# M710X.net
KiCad netlist of a schematic drawn in EAGLE
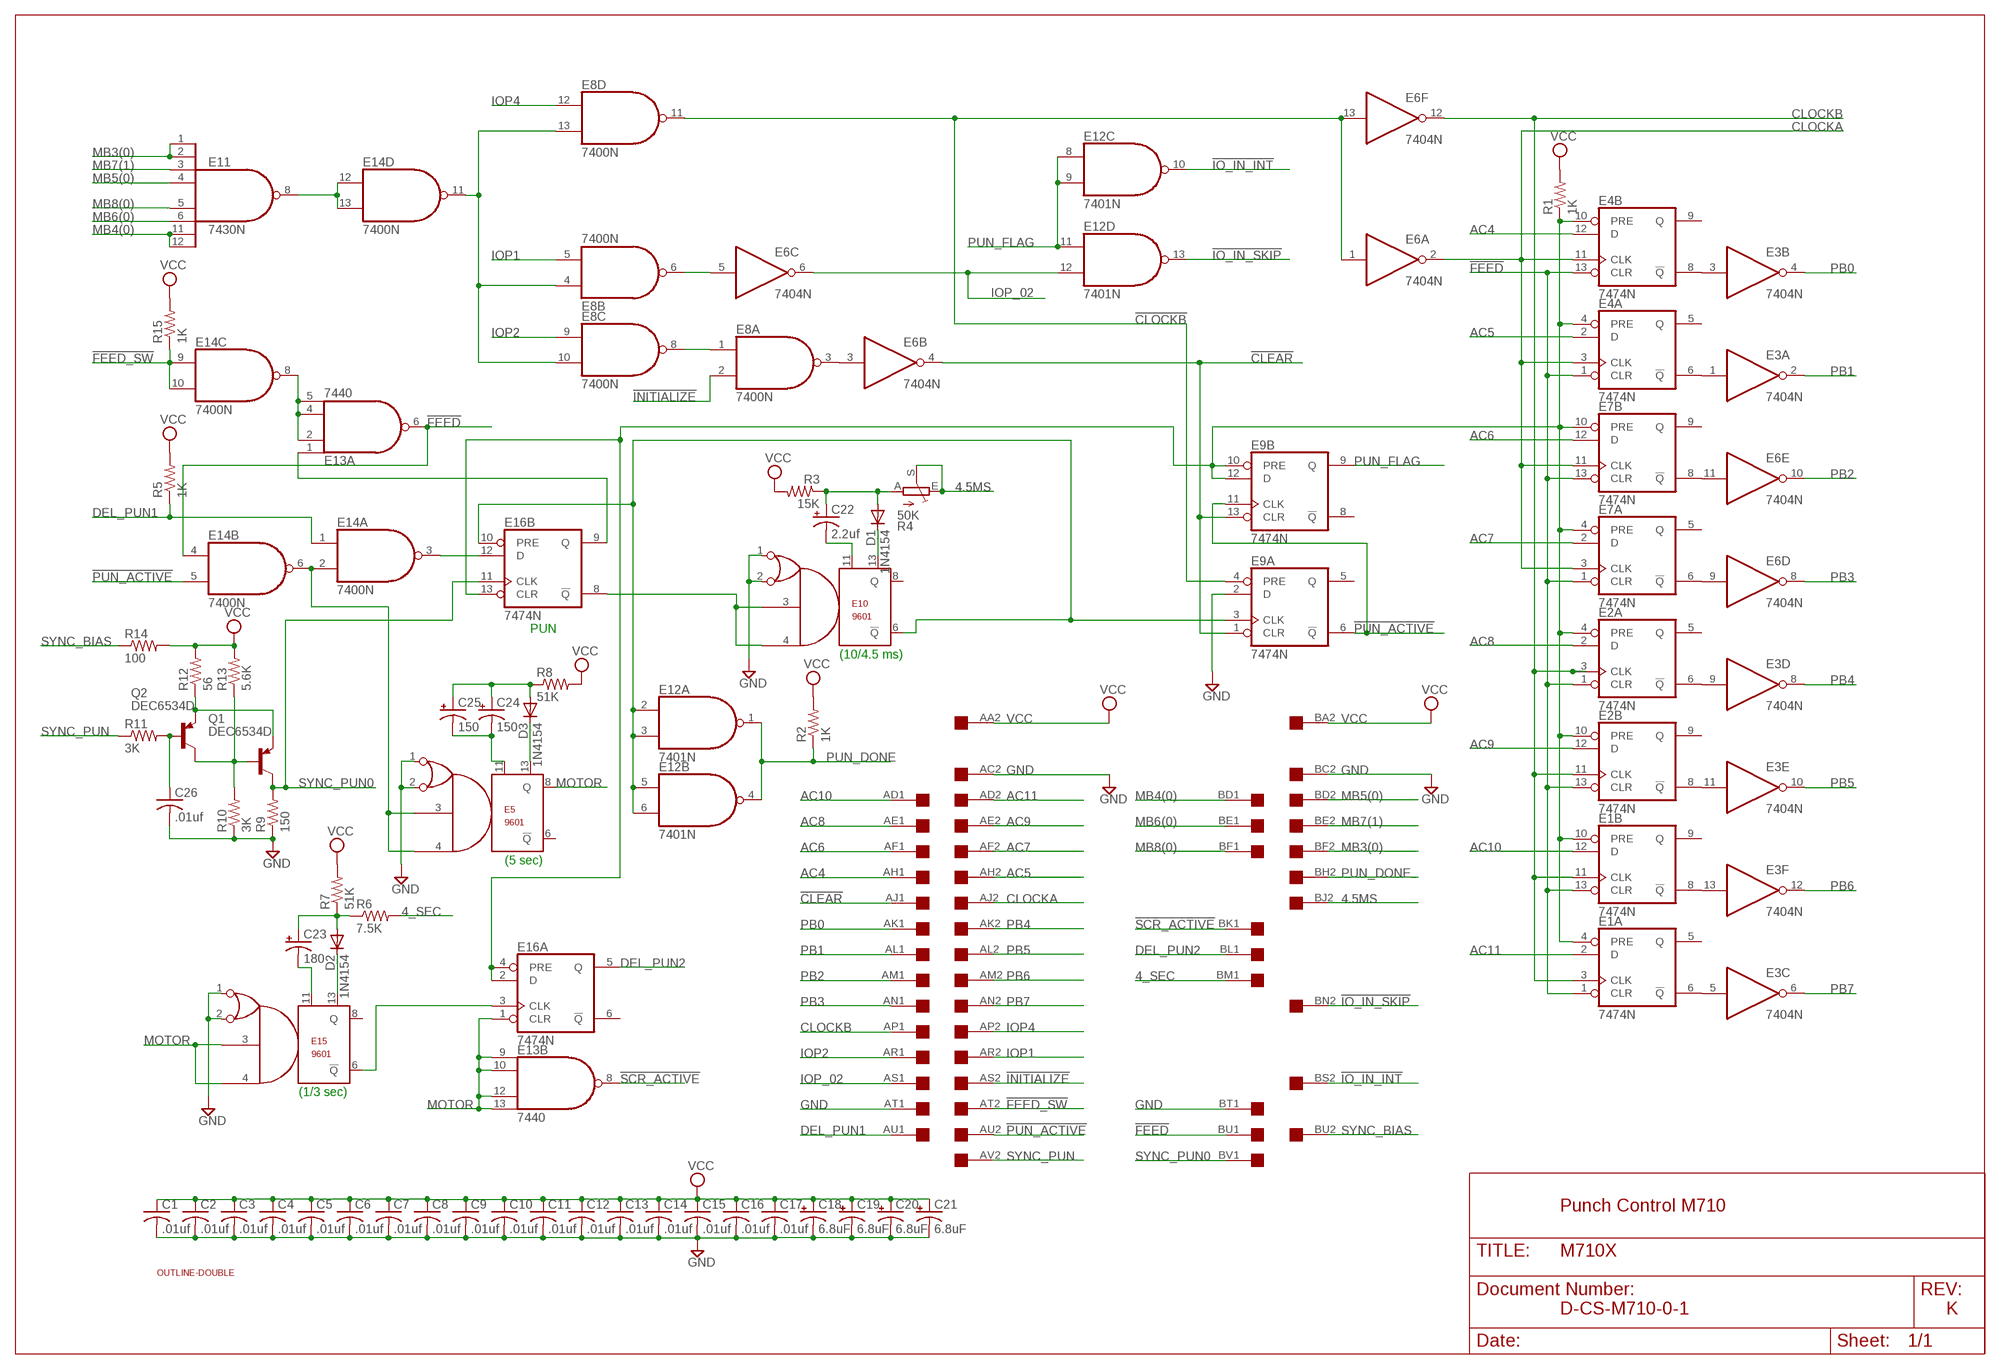
[diagram p0: schematic, sheet 1]

(export (version "E")
  (design (tool "Eeschema 10.0.6"))
  (components
    (comp (ref "C1")
      (value ".01uf")
      (footprint "eagle-import:C050-025X075")
      (libsource (lib "eagle-import") (part "C-US050-025X075"))
    )
    (comp (ref "C2")
      (value ".01uf")
      (footprint "eagle-import:C050-025X075")
      (libsource (lib "eagle-import") (part "C-US050-025X075"))
    )
    (comp (ref "C3")
      (value ".01uf")
      (footprint "eagle-import:C050-025X075")
      (libsource (lib "eagle-import") (part "C-US050-025X075"))
    )
    (comp (ref "C4")
      (value ".01uf")
      (footprint "eagle-import:C050-025X075")
      (libsource (lib "eagle-import") (part "C-US050-025X075"))
    )
    (comp (ref "C5")
      (value ".01uf")
      (footprint "eagle-import:C050-025X075")
      (libsource (lib "eagle-import") (part "C-US050-025X075"))
    )
    (comp (ref "C6")
      (value ".01uf")
      (footprint "eagle-import:C050-025X075")
      (libsource (lib "eagle-import") (part "C-US050-025X075"))
    )
    (comp (ref "C7")
      (value ".01uf")
      (footprint "eagle-import:C050-025X075")
      (libsource (lib "eagle-import") (part "C-US050-025X075"))
    )
    (comp (ref "C8")
      (value ".01uf")
      (footprint "eagle-import:C050-025X075")
      (libsource (lib "eagle-import") (part "C-US050-025X075"))
    )
    (comp (ref "C9")
      (value ".01uf")
      (footprint "eagle-import:C050-025X075")
      (libsource (lib "eagle-import") (part "C-US050-025X075"))
    )
    (comp (ref "C10")
      (value ".01uf")
      (footprint "eagle-import:C050-025X075")
      (libsource (lib "eagle-import") (part "C-US050-025X075"))
    )
    (comp (ref "C11")
      (value ".01uf")
      (footprint "eagle-import:C050-025X075")
      (libsource (lib "eagle-import") (part "C-US050-025X075"))
    )
    (comp (ref "C12")
      (value ".01uf")
      (footprint "eagle-import:C050-025X075")
      (libsource (lib "eagle-import") (part "C-US050-025X075"))
    )
    (comp (ref "C13")
      (value ".01uf")
      (footprint "eagle-import:C050-025X075")
      (libsource (lib "eagle-import") (part "C-US050-025X075"))
    )
    (comp (ref "C14")
      (value ".01uf")
      (footprint "eagle-import:C050-025X075")
      (libsource (lib "eagle-import") (part "C-US050-025X075"))
    )
    (comp (ref "C15")
      (value ".01uf")
      (footprint "eagle-import:C050-025X075")
      (libsource (lib "eagle-import") (part "C-US050-025X075"))
    )
    (comp (ref "C16")
      (value ".01uf")
      (footprint "eagle-import:C050-025X075")
      (libsource (lib "eagle-import") (part "C-US050-025X075"))
    )
    (comp (ref "C17")
      (value ".01uf")
      (footprint "eagle-import:C050-025X075")
      (libsource (lib "eagle-import") (part "C-US050-025X075"))
    )
    (comp (ref "C18")
      (value "6.8uF")
      (footprint "eagle-import:E12-8")
      (libsource (lib "eagle-import") (part "CPOL-USE20-8AXIAL"))
    )
    (comp (ref "C19")
      (value "6.8uF")
      (footprint "eagle-import:E12-8")
      (libsource (lib "eagle-import") (part "CPOL-USE20-8AXIAL"))
    )
    (comp (ref "C20")
      (value "6.8uF")
      (footprint "eagle-import:E12-8")
      (libsource (lib "eagle-import") (part "CPOL-USE20-8AXIAL"))
    )
    (comp (ref "C21")
      (value "6.8uF")
      (footprint "eagle-import:E12-8")
      (libsource (lib "eagle-import") (part "CPOL-USE20-8AXIAL"))
    )
    (comp (ref "C22")
      (value "2.2uf")
      (footprint "eagle-import:E15-5")
      (libsource (lib "eagle-import") (part "CPOL-USE15-5AXIAL"))
    )
    (comp (ref "C23")
      (value "180")
      (footprint "eagle-import:E12-8")
      (libsource (lib "eagle-import") (part "CPOL-USE20-8AXIAL"))
    )
    (comp (ref "C24")
      (value "150")
      (footprint "eagle-import:E22-6")
      (libsource (lib "eagle-import") (part "CPOL-USE22-6AXIAL"))
    )
    (comp (ref "C25")
      (value "150")
      (footprint "eagle-import:E22-6")
      (libsource (lib "eagle-import") (part "CPOL-USE22-6AXIAL"))
    )
    (comp (ref "C26")
      (value ".01uf")
      (footprint "eagle-import:C050-025X075")
      (libsource (lib "eagle-import") (part "C-US050-025X075"))
    )
    (comp (ref "D1")
      (value "1N4154")
      (footprint "eagle-import:DO41-10")
      (libsource (lib "eagle-import") (part "1N4004"))
    )
    (comp (ref "D2")
      (value "1N4154")
      (footprint "eagle-import:DO41-10")
      (libsource (lib "eagle-import") (part "1N4004"))
    )
    (comp (ref "D3")
      (value "1N4154")
      (footprint "eagle-import:DO41-10")
      (libsource (lib "eagle-import") (part "1N4004"))
    )
    (comp (ref "E1")
      (value "7474N")
      (footprint "eagle-import:DIL14")
      (libsource (lib "eagle-import") (part "7474NS"))
    )
    (comp (ref "E2")
      (value "7474N")
      (footprint "eagle-import:DIL14")
      (libsource (lib "eagle-import") (part "7474NS"))
    )
    (comp (ref "E3")
      (value "7404N")
      (footprint "eagle-import:DIL14")
      (libsource (lib "eagle-import") (part "7404N"))
    )
    (comp (ref "E4")
      (value "7474N")
      (footprint "eagle-import:DIL14")
      (libsource (lib "eagle-import") (part "7474NS"))
    )
    (comp (ref "E5")
      (value "9601")
      (footprint "eagle-import:DIL14")
      (libsource (lib "eagle-import") (part "9601"))
    )
    (comp (ref "E6")
      (value "7404N")
      (footprint "eagle-import:DIL14")
      (libsource (lib "eagle-import") (part "7404N"))
    )
    (comp (ref "E7")
      (value "7474N")
      (footprint "eagle-import:DIL14")
      (libsource (lib "eagle-import") (part "7474NS"))
    )
    (comp (ref "E8")
      (value "7400N")
      (footprint "eagle-import:DIL14")
      (libsource (lib "eagle-import") (part "7400N"))
    )
    (comp (ref "E9")
      (value "7474N")
      (footprint "eagle-import:DIL14")
      (libsource (lib "eagle-import") (part "7474NS"))
    )
    (comp (ref "E10")
      (value "9601")
      (footprint "eagle-import:DIL14")
      (libsource (lib "eagle-import") (part "9601"))
    )
    (comp (ref "E11")
      (value "7430N")
      (footprint "eagle-import:DIL14")
      (libsource (lib "eagle-import") (part "7430N"))
    )
    (comp (ref "E12")
      (value "7401N")
      (footprint "eagle-import:DIL14")
      (libsource (lib "eagle-import") (part "7401NLS"))
    )
    (comp (ref "E13")
      (value "7440")
      (footprint "eagle-import:DIL14")
      (libsource (lib "eagle-import") (part "7420NS"))
    )
    (comp (ref "E14")
      (value "7400N")
      (footprint "eagle-import:DIL14")
      (libsource (lib "eagle-import") (part "7400N"))
    )
    (comp (ref "E15")
      (value "9601")
      (footprint "eagle-import:DIL14")
      (libsource (lib "eagle-import") (part "9601"))
    )
    (comp (ref "E16")
      (value "7474N")
      (footprint "eagle-import:DIL14")
      (libsource (lib "eagle-import") (part "7474NS"))
    )
    (comp (ref "Q1")
      (value "DEC6534D")
      (footprint "eagle-import:TO5")
      (libsource (lib "eagle-import") (part "2N2905"))
    )
    (comp (ref "Q2")
      (value "DEC6534D")
      (footprint "eagle-import:TO5")
      (libsource (lib "eagle-import") (part "2N2905"))
    )
    (comp (ref "R1")
      (value "1K")
      (footprint "eagle-import:0207_10")
      (libsource (lib "eagle-import") (part "R-US_0207/10"))
    )
    (comp (ref "R2")
      (value "1K")
      (footprint "eagle-import:0207_10")
      (libsource (lib "eagle-import") (part "R-US_0207/10"))
    )
    (comp (ref "R3")
      (value "15K")
      (footprint "eagle-import:0207_10")
      (libsource (lib "eagle-import") (part "R-US_0207/10"))
    )
    (comp (ref "R4")
      (value "50K")
      (footprint "eagle-import:RJ6")
      (libsource (lib "eagle-import") (part "TRIM_EU-RJ6"))
    )
    (comp (ref "R5")
      (value "1K")
      (footprint "eagle-import:0207_10")
      (libsource (lib "eagle-import") (part "R-US_0207/10"))
    )
    (comp (ref "R6")
      (value "7.5K")
      (footprint "eagle-import:0207_10")
      (libsource (lib "eagle-import") (part "R-US_0207/10"))
    )
    (comp (ref "R7")
      (value "51K")
      (footprint "eagle-import:0207_10")
      (libsource (lib "eagle-import") (part "R-US_0207/10"))
    )
    (comp (ref "R8")
      (value "51K")
      (footprint "eagle-import:0207_10")
      (libsource (lib "eagle-import") (part "R-US_0207/10"))
    )
    (comp (ref "R9")
      (value "150")
      (footprint "eagle-import:0207_10")
      (libsource (lib "eagle-import") (part "R-US_0207/10"))
    )
    (comp (ref "R10")
      (value "3K")
      (footprint "eagle-import:0207_10")
      (libsource (lib "eagle-import") (part "R-US_0207/10"))
    )
    (comp (ref "R11")
      (value "3K")
      (footprint "eagle-import:0207_10")
      (libsource (lib "eagle-import") (part "R-US_0207/10"))
    )
    (comp (ref "R12")
      (value "56")
      (footprint "eagle-import:0207_10")
      (libsource (lib "eagle-import") (part "R-US_0207/10"))
    )
    (comp (ref "R13")
      (value "5.6K")
      (footprint "eagle-import:0207_10")
      (libsource (lib "eagle-import") (part "R-US_0207/10"))
    )
    (comp (ref "R14")
      (value "100")
      (footprint "eagle-import:0207_10")
      (libsource (lib "eagle-import") (part "R-US_0207/10"))
    )
    (comp (ref "R15")
      (value "1K")
      (footprint "eagle-import:0207_10")
      (libsource (lib "eagle-import") (part "R-US_0207/10"))
    )
    (comp (ref "U$1")
      (value "OUTLINE-DOUBLE")
      (footprint "eagle-import:DOUBLE")
      (libsource (lib "eagle-import") (part "OUTLINE-DOUBLE"))
    )
    (comp (ref "U$2")
      (value "DOUBLE")
      (footprint "eagle-import:EDGE-CON4")
      (libsource (lib "eagle-import") (part "DOUBLE"))
    )
  )
  (nets
    (net (code "1") (name "/4.5MS") (class "Default")
      (node (ref "R4") (pin "E") (pinfunction "E_E") (pintype "passive"))
      (node (ref "R4") (pin "S") (pinfunction "S_S") (pintype "passive"))
      (node (ref "U$2") (pin "BJ2") (pinfunction "1_BJ2") (pintype "bidirectional"))
    )
    (net (code "2") (name "/4_SEC") (class "Default")
      (node (ref "R6") (pin "2") (pinfunction "2_2") (pintype "passive"))
      (node (ref "U$2") (pin "BM1") (pinfunction "1_BM1") (pintype "bidirectional"))
    )
    (net (code "3") (name "/AC4") (class "Default")
      (node (ref "E4") (pin "12") (pinfunction "D_12") (pintype "input"))
      (node (ref "U$2") (pin "AH1") (pinfunction "1_AH1") (pintype "bidirectional"))
    )
    (net (code "4") (name "/AC5") (class "Default")
      (node (ref "E4") (pin "2") (pinfunction "D_2") (pintype "input"))
      (node (ref "U$2") (pin "AH2") (pinfunction "1_AH2") (pintype "bidirectional"))
    )
    (net (code "5") (name "/AC6") (class "Default")
      (node (ref "E7") (pin "12") (pinfunction "D_12") (pintype "input"))
      (node (ref "U$2") (pin "AF1") (pinfunction "1_AF1") (pintype "bidirectional"))
    )
    (net (code "6") (name "/AC7") (class "Default")
      (node (ref "E7") (pin "2") (pinfunction "D_2") (pintype "input"))
      (node (ref "U$2") (pin "AF2") (pinfunction "1_AF2") (pintype "bidirectional"))
    )
    (net (code "7") (name "/AC8") (class "Default")
      (node (ref "E2") (pin "2") (pinfunction "D_2") (pintype "input"))
      (node (ref "U$2") (pin "AE1") (pinfunction "1_AE1") (pintype "bidirectional"))
    )
    (net (code "8") (name "/AC9") (class "Default")
      (node (ref "E2") (pin "12") (pinfunction "D_12") (pintype "input"))
      (node (ref "U$2") (pin "AE2") (pinfunction "1_AE2") (pintype "bidirectional"))
    )
    (net (code "9") (name "/AC10") (class "Default")
      (node (ref "E1") (pin "12") (pinfunction "D_12") (pintype "input"))
      (node (ref "U$2") (pin "AD1") (pinfunction "1_AD1") (pintype "bidirectional"))
    )
    (net (code "10") (name "/AC11") (class "Default")
      (node (ref "E1") (pin "2") (pinfunction "D_2") (pintype "input"))
      (node (ref "U$2") (pin "AD2") (pinfunction "1_AD2") (pintype "bidirectional"))
    )
    (net (code "11") (name "/CLOCKA") (class "Default")
      (node (ref "E4") (pin "11") (pinfunction "CLK_11") (pintype "input"))
      (node (ref "E4") (pin "3") (pinfunction "CLK_3") (pintype "input"))
      (node (ref "E6") (pin "2") (pinfunction "O_2") (pintype "output"))
      (node (ref "E7") (pin "11") (pinfunction "CLK_11") (pintype "input"))
      (node (ref "E7") (pin "3") (pinfunction "CLK_3") (pintype "input"))
      (node (ref "U$2") (pin "AJ2") (pinfunction "1_AJ2") (pintype "bidirectional"))
    )
    (net (code "12") (name "/CLOCKB") (class "Default")
      (node (ref "E1") (pin "11") (pinfunction "CLK_11") (pintype "input"))
      (node (ref "E1") (pin "3") (pinfunction "CLK_3") (pintype "input"))
      (node (ref "E2") (pin "11") (pinfunction "CLK_11") (pintype "input"))
      (node (ref "E2") (pin "3") (pinfunction "CLK_3") (pintype "input"))
      (node (ref "E6") (pin "12") (pinfunction "O_12") (pintype "output"))
      (node (ref "U$2") (pin "AP1") (pinfunction "1_AP1") (pintype "bidirectional"))
    )
    (net (code "13") (name "/DEL_PUN1") (class "Default")
      (node (ref "E14") (pin "1") (pinfunction "I0_1") (pintype "input"))
      (node (ref "R5") (pin "1") (pinfunction "1_1") (pintype "passive"))
      (node (ref "U$2") (pin "AU1") (pinfunction "1_AU1") (pintype "bidirectional"))
    )
    (net (code "14") (name "/DEL_PUN2") (class "Default")
      (node (ref "E16") (pin "5") (pinfunction "Q_5") (pintype "output"))
      (node (ref "U$2") (pin "BL1") (pinfunction "1_BL1") (pintype "bidirectional"))
    )
    (net (code "15") (name "/IOP1") (class "Default")
      (node (ref "E8") (pin "5") (pinfunction "I1_5") (pintype "input"))
      (node (ref "U$2") (pin "AR2") (pinfunction "1_AR2") (pintype "bidirectional"))
    )
    (net (code "16") (name "/IOP2") (class "Default")
      (node (ref "E8") (pin "9") (pinfunction "I0_9") (pintype "input"))
      (node (ref "U$2") (pin "AR1") (pinfunction "1_AR1") (pintype "bidirectional"))
    )
    (net (code "17") (name "/IOP4") (class "Default")
      (node (ref "E8") (pin "12") (pinfunction "I0_12") (pintype "input"))
      (node (ref "U$2") (pin "AP2") (pinfunction "1_AP2") (pintype "bidirectional"))
    )
    (net (code "18") (name "/IOP_02") (class "Default")
      (node (ref "E12") (pin "12") (pinfunction "I1_12") (pintype "input"))
      (node (ref "E6") (pin "6") (pinfunction "O_6") (pintype "output"))
      (node (ref "U$2") (pin "AS1") (pinfunction "1_AS1") (pintype "bidirectional"))
    )
    (net (code "19") (name "/MB3(0)") (class "Default")
      (node (ref "E11") (pin "1") (pinfunction "I0_1") (pintype "input"))
      (node (ref "E11") (pin "2") (pinfunction "I1_2") (pintype "input"))
      (node (ref "U$2") (pin "BF2") (pinfunction "1_BF2") (pintype "bidirectional"))
    )
    (net (code "20") (name "/MB4(0)") (class "Default")
      (node (ref "E11") (pin "11") (pinfunction "I6_11") (pintype "input"))
      (node (ref "E11") (pin "12") (pinfunction "I7_12") (pintype "input"))
      (node (ref "U$2") (pin "BD1") (pinfunction "1_BD1") (pintype "bidirectional"))
    )
    (net (code "21") (name "/MB5(0)") (class "Default")
      (node (ref "E11") (pin "4") (pinfunction "I3_4") (pintype "input"))
      (node (ref "U$2") (pin "BD2") (pinfunction "1_BD2") (pintype "bidirectional"))
    )
    (net (code "22") (name "/MB6(0)") (class "Default")
      (node (ref "E11") (pin "6") (pinfunction "I5_6") (pintype "input"))
      (node (ref "U$2") (pin "BE1") (pinfunction "1_BE1") (pintype "bidirectional"))
    )
    (net (code "23") (name "/MB7(1)") (class "Default")
      (node (ref "E11") (pin "3") (pinfunction "I2_3") (pintype "input"))
      (node (ref "U$2") (pin "BE2") (pinfunction "1_BE2") (pintype "bidirectional"))
    )
    (net (code "24") (name "/MB8(0)") (class "Default")
      (node (ref "E11") (pin "5") (pinfunction "I4_5") (pintype "input"))
      (node (ref "U$2") (pin "BF1") (pinfunction "1_BF1") (pintype "bidirectional"))
    )
    (net (code "25") (name "/MOTOR") (class "Default")
      (node (ref "E13") (pin "10") (pinfunction "I1_10") (pintype "input"))
      (node (ref "E13") (pin "12") (pinfunction "I2_12") (pintype "input"))
      (node (ref "E13") (pin "13") (pinfunction "I3_13") (pintype "input"))
      (node (ref "E13") (pin "9") (pinfunction "I0_9") (pintype "input"))
      (node (ref "E15") (pin "3") (pinfunction "P$3_3") (pintype "input"))
      (node (ref "E15") (pin "4") (pinfunction "P$4_4") (pintype "input"))
      (node (ref "E16") (pin "1") (pinfunction "CLR_1") (pintype "input"))
      (node (ref "E5") (pin "8") (pinfunction "Q_8") (pintype "output"))
    )
    (net (code "26") (name "/PB0") (class "Default")
      (node (ref "E3") (pin "4") (pinfunction "O_4") (pintype "output"))
      (node (ref "U$2") (pin "AK1") (pinfunction "1_AK1") (pintype "bidirectional"))
    )
    (net (code "27") (name "/PB1") (class "Default")
      (node (ref "E3") (pin "2") (pinfunction "O_2") (pintype "output"))
      (node (ref "U$2") (pin "AL1") (pinfunction "1_AL1") (pintype "bidirectional"))
    )
    (net (code "28") (name "/PB2") (class "Default")
      (node (ref "E6") (pin "10") (pinfunction "O_10") (pintype "output"))
      (node (ref "U$2") (pin "AM1") (pinfunction "1_AM1") (pintype "bidirectional"))
    )
    (net (code "29") (name "/PB3") (class "Default")
      (node (ref "E6") (pin "8") (pinfunction "O_8") (pintype "output"))
      (node (ref "U$2") (pin "AN1") (pinfunction "1_AN1") (pintype "bidirectional"))
    )
    (net (code "30") (name "/PB4") (class "Default")
      (node (ref "E3") (pin "8") (pinfunction "O_8") (pintype "output"))
      (node (ref "U$2") (pin "AK2") (pinfunction "1_AK2") (pintype "bidirectional"))
    )
    (net (code "31") (name "/PB5") (class "Default")
      (node (ref "E3") (pin "10") (pinfunction "O_10") (pintype "output"))
      (node (ref "U$2") (pin "AL2") (pinfunction "1_AL2") (pintype "bidirectional"))
    )
    (net (code "32") (name "/PB6") (class "Default")
      (node (ref "E3") (pin "12") (pinfunction "O_12") (pintype "output"))
      (node (ref "U$2") (pin "AM2") (pinfunction "1_AM2") (pintype "bidirectional"))
    )
    (net (code "33") (name "/PB7") (class "Default")
      (node (ref "E3") (pin "6") (pinfunction "O_6") (pintype "output"))
      (node (ref "U$2") (pin "AN2") (pinfunction "1_AN2") (pintype "bidirectional"))
    )
    (net (code "34") (name "/PUN_DONE") (class "Default")
      (node (ref "E12") (pin "1") (pinfunction "O_1") (pintype "open_collector"))
      (node (ref "E12") (pin "4") (pinfunction "O_4") (pintype "open_collector"))
      (node (ref "R2") (pin "1") (pinfunction "1_1") (pintype "passive"))
      (node (ref "U$2") (pin "BH2") (pinfunction "1_BH2") (pintype "bidirectional"))
    )
    (net (code "35") (name "/PUN_FLAG") (class "Default")
      (node (ref "E12") (pin "11") (pinfunction "I0_11") (pintype "input"))
      (node (ref "E12") (pin "8") (pinfunction "I0_8") (pintype "input"))
      (node (ref "E12") (pin "9") (pinfunction "I1_9") (pintype "input"))
      (node (ref "E9") (pin "9") (pinfunction "Q_9") (pintype "output"))
    )
    (net (code "36") (name "/SYNC_BIAS") (class "Default")
      (node (ref "R14") (pin "1") (pinfunction "1_1") (pintype "passive"))
      (node (ref "U$2") (pin "BU2") (pinfunction "1_BU2") (pintype "bidirectional"))
    )
    (net (code "37") (name "/SYNC_PUN") (class "Default")
      (node (ref "R11") (pin "1") (pinfunction "1_1") (pintype "passive"))
      (node (ref "U$2") (pin "AV2") (pinfunction "1_AV2") (pintype "bidirectional"))
    )
    (net (code "38") (name "/SYNC_PUN0") (class "Default")
      (node (ref "E16") (pin "11") (pinfunction "CLK_11") (pintype "input"))
      (node (ref "Q1") (pin "3") (pinfunction "C_3") (pintype "passive"))
      (node (ref "R9") (pin "2") (pinfunction "2_2") (pintype "passive"))
      (node (ref "U$2") (pin "BV1") (pinfunction "1_BV1") (pintype "bidirectional"))
    )
    (net (code "39") (name "/~{CLEAR}") (class "Default")
      (node (ref "E6") (pin "4") (pinfunction "O_4") (pintype "output"))
      (node (ref "E9") (pin "1") (pinfunction "CLR_1") (pintype "input"))
      (node (ref "E9") (pin "13") (pinfunction "CLR_13") (pintype "input"))
      (node (ref "U$2") (pin "AJ1") (pinfunction "1_AJ1") (pintype "bidirectional"))
    )
    (net (code "40") (name "/~{CLOCKB}") (class "Default")
      (node (ref "E6") (pin "1") (pinfunction "I_1") (pintype "input"))
      (node (ref "E6") (pin "13") (pinfunction "I_13") (pintype "input"))
      (node (ref "E8") (pin "11") (pinfunction "O_11") (pintype "output"))
      (node (ref "E9") (pin "4") (pinfunction "PRE_4") (pintype "input"))
    )
    (net (code "41") (name "/~{FEED_SW}") (class "Default")
      (node (ref "E14") (pin "10") (pinfunction "I1_10") (pintype "input"))
      (node (ref "E14") (pin "9") (pinfunction "I0_9") (pintype "input"))
      (node (ref "R15") (pin "1") (pinfunction "1_1") (pintype "passive"))
      (node (ref "U$2") (pin "AT2") (pinfunction "1_AT2") (pintype "bidirectional"))
    )
    (net (code "42") (name "/~{FEED}") (class "Default")
      (node (ref "E1") (pin "1") (pinfunction "CLR_1") (pintype "input"))
      (node (ref "E1") (pin "13") (pinfunction "CLR_13") (pintype "input"))
      (node (ref "E13") (pin "6") (pinfunction "O_6") (pintype "output"))
      (node (ref "E14") (pin "4") (pinfunction "I0_4") (pintype "input"))
      (node (ref "E2") (pin "1") (pinfunction "CLR_1") (pintype "input"))
      (node (ref "E2") (pin "13") (pinfunction "CLR_13") (pintype "input"))
      (node (ref "E4") (pin "1") (pinfunction "CLR_1") (pintype "input"))
      (node (ref "E4") (pin "13") (pinfunction "CLR_13") (pintype "input"))
      (node (ref "E7") (pin "1") (pinfunction "CLR_1") (pintype "input"))
      (node (ref "E7") (pin "13") (pinfunction "CLR_13") (pintype "input"))
      (node (ref "U$2") (pin "BU1") (pinfunction "1_BU1") (pintype "bidirectional"))
    )
    (net (code "43") (name "/~{INITIALIZE}") (class "Default")
      (node (ref "E8") (pin "2") (pinfunction "I1_2") (pintype "input"))
      (node (ref "U$2") (pin "AS2") (pinfunction "1_AS2") (pintype "bidirectional"))
    )
    (net (code "44") (name "/~{IO_IN_INT}") (class "Default")
      (node (ref "E12") (pin "10") (pinfunction "O_10") (pintype "open_collector"))
      (node (ref "U$2") (pin "BS2") (pinfunction "1_BS2") (pintype "bidirectional"))
    )
    (net (code "45") (name "/~{IO_IN_SKIP}") (class "Default")
      (node (ref "E12") (pin "13") (pinfunction "O_13") (pintype "open_collector"))
      (node (ref "U$2") (pin "BN2") (pinfunction "1_BN2") (pintype "bidirectional"))
    )
    (net (code "46") (name "/~{PUN_ACTIVE}") (class "Default")
      (node (ref "E14") (pin "5") (pinfunction "I1_5") (pintype "input"))
      (node (ref "E9") (pin "11") (pinfunction "CLK_11") (pintype "input"))
      (node (ref "E9") (pin "6") (pinfunction "~{Q}_6") (pintype "output"))
      (node (ref "U$2") (pin "AU2") (pinfunction "1_AU2") (pintype "bidirectional"))
    )
    (net (code "47") (name "/~{SCR_ACTIVE}") (class "Default")
      (node (ref "E13") (pin "8") (pinfunction "O_8") (pintype "output"))
      (node (ref "U$2") (pin "BK1") (pinfunction "1_BK1") (pintype "bidirectional"))
    )
    (net (code "48") (name "GND") (class "Default")
      (node (ref "C1") (pin "2") (pinfunction "2_2") (pintype "passive"))
      (node (ref "C10") (pin "2") (pinfunction "2_2") (pintype "passive"))
      (node (ref "C11") (pin "2") (pinfunction "2_2") (pintype "passive"))
      (node (ref "C12") (pin "2") (pinfunction "2_2") (pintype "passive"))
      (node (ref "C13") (pin "2") (pinfunction "2_2") (pintype "passive"))
      (node (ref "C14") (pin "2") (pinfunction "2_2") (pintype "passive"))
      (node (ref "C15") (pin "2") (pinfunction "2_2") (pintype "passive"))
      (node (ref "C16") (pin "2") (pinfunction "2_2") (pintype "passive"))
      (node (ref "C17") (pin "2") (pinfunction "2_2") (pintype "passive"))
      (node (ref "C18") (pin "-") (pinfunction "-_-") (pintype "passive"))
      (node (ref "C19") (pin "-") (pinfunction "-_-") (pintype "passive"))
      (node (ref "C2") (pin "2") (pinfunction "2_2") (pintype "passive"))
      (node (ref "C20") (pin "-") (pinfunction "-_-") (pintype "passive"))
      (node (ref "C21") (pin "-") (pinfunction "-_-") (pintype "passive"))
      (node (ref "C26") (pin "2") (pinfunction "2_2") (pintype "passive"))
      (node (ref "C3") (pin "2") (pinfunction "2_2") (pintype "passive"))
      (node (ref "C4") (pin "2") (pinfunction "2_2") (pintype "passive"))
      (node (ref "C5") (pin "2") (pinfunction "2_2") (pintype "passive"))
      (node (ref "C6") (pin "2") (pinfunction "2_2") (pintype "passive"))
      (node (ref "C7") (pin "2") (pinfunction "2_2") (pintype "passive"))
      (node (ref "C8") (pin "2") (pinfunction "2_2") (pintype "passive"))
      (node (ref "C9") (pin "2") (pinfunction "2_2") (pintype "passive"))
      (node (ref "E10") (pin "1") (pinfunction "P$1_1") (pintype "input"))
      (node (ref "E10") (pin "2") (pinfunction "P$2_2") (pintype "input"))
      (node (ref "E15") (pin "1") (pinfunction "P$1_1") (pintype "input"))
      (node (ref "E15") (pin "2") (pinfunction "P$2_2") (pintype "input"))
      (node (ref "E5") (pin "1") (pinfunction "P$1_1") (pintype "input"))
      (node (ref "E5") (pin "2") (pinfunction "P$2_2") (pintype "input"))
      (node (ref "E9") (pin "2") (pinfunction "D_2") (pintype "input"))
      (node (ref "R10") (pin "1") (pinfunction "1_1") (pintype "passive"))
      (node (ref "R9") (pin "1") (pinfunction "1_1") (pintype "passive"))
      (node (ref "U$2") (pin "AC2") (pinfunction "1_AC2") (pintype "bidirectional"))
      (node (ref "U$2") (pin "AT1") (pinfunction "1_AT1") (pintype "bidirectional"))
      (node (ref "U$2") (pin "BC2") (pinfunction "1_BC2") (pintype "bidirectional"))
      (node (ref "U$2") (pin "BT1") (pinfunction "1_BT1") (pintype "bidirectional"))
    )
    (net (code "49") (name "Net-(C22-Pad+)") (class "Default")
      (node (ref "C22") (pin "+") (pinfunction "+_+") (pintype "passive"))
      (node (ref "D1") (pin "A") (pinfunction "A_A") (pintype "passive"))
      (node (ref "R3") (pin "1") (pinfunction "1_1") (pintype "passive"))
      (node (ref "R4") (pin "A") (pinfunction "A_A") (pintype "passive"))
    )
    (net (code "50") (name "Net-(C23-Pad+)") (class "Default")
      (node (ref "C23") (pin "+") (pinfunction "+_+") (pintype "passive"))
      (node (ref "D2") (pin "A") (pinfunction "A_A") (pintype "passive"))
      (node (ref "R6") (pin "1") (pinfunction "1_1") (pintype "passive"))
      (node (ref "R7") (pin "1") (pinfunction "1_1") (pintype "passive"))
    )
    (net (code "51") (name "Net-(C24-Pad+)") (class "Default")
      (node (ref "C24") (pin "+") (pinfunction "+_+") (pintype "passive"))
      (node (ref "C25") (pin "+") (pinfunction "+_+") (pintype "passive"))
      (node (ref "D3") (pin "A") (pinfunction "A_A") (pintype "passive"))
      (node (ref "R8") (pin "1") (pinfunction "1_1") (pintype "passive"))
    )
    (net (code "52") (name "Net-(E1A-~{Q})") (class "Default")
      (node (ref "E1") (pin "6") (pinfunction "~{Q}_6") (pintype "output"))
      (node (ref "E3") (pin "5") (pinfunction "I_5") (pintype "input"))
    )
    (net (code "53") (name "Net-(E1B-~{Q})") (class "Default")
      (node (ref "E1") (pin "8") (pinfunction "~{Q}_8") (pintype "output"))
      (node (ref "E3") (pin "13") (pinfunction "I_13") (pintype "input"))
    )
    (net (code "54") (name "Net-(E2A-~{Q})") (class "Default")
      (node (ref "E2") (pin "6") (pinfunction "~{Q}_6") (pintype "output"))
      (node (ref "E3") (pin "9") (pinfunction "I_9") (pintype "input"))
    )
    (net (code "55") (name "Net-(E2B-~{Q})") (class "Default")
      (node (ref "E2") (pin "8") (pinfunction "~{Q}_8") (pintype "output"))
      (node (ref "E3") (pin "11") (pinfunction "I_11") (pintype "input"))
    )
    (net (code "56") (name "Net-(E3A-I)") (class "Default")
      (node (ref "E3") (pin "1") (pinfunction "I_1") (pintype "input"))
      (node (ref "E4") (pin "6") (pinfunction "~{Q}_6") (pintype "output"))
    )
    (net (code "57") (name "Net-(E3B-I)") (class "Default")
      (node (ref "E3") (pin "3") (pinfunction "I_3") (pintype "input"))
      (node (ref "E4") (pin "8") (pinfunction "~{Q}_8") (pintype "output"))
    )
    (net (code "58") (name "Net-(E5A-P$5)") (class "Default")
      (node (ref "C24") (pin "-") (pinfunction "-_-") (pintype "passive"))
      (node (ref "C25") (pin "-") (pinfunction "-_-") (pintype "passive"))
      (node (ref "E5") (pin "11") (pinfunction "P$5_11") (pintype "bidirectional"))
    )
    (net (code "59") (name "Net-(E5A-P$6)") (class "Default")
      (node (ref "D3") (pin "C") (pinfunction "C_C") (pintype "passive"))
      (node (ref "E5") (pin "13") (pinfunction "P$6_13") (pintype "bidirectional"))
    )
    (net (code "60") (name "Net-(E6B-I)") (class "Default")
      (node (ref "E6") (pin "3") (pinfunction "I_3") (pintype "input"))
      (node (ref "E8") (pin "3") (pinfunction "O_3") (pintype "output"))
    )
    (net (code "61") (name "Net-(E6C-I)") (class "Default")
      (node (ref "E6") (pin "5") (pinfunction "I_5") (pintype "input"))
      (node (ref "E8") (pin "6") (pinfunction "O_6") (pintype "output"))
    )
    (net (code "62") (name "Net-(E6D-I)") (class "Default")
      (node (ref "E6") (pin "9") (pinfunction "I_9") (pintype "input"))
      (node (ref "E7") (pin "6") (pinfunction "~{Q}_6") (pintype "output"))
    )
    (net (code "63") (name "Net-(E6E-I)") (class "Default")
      (node (ref "E6") (pin "11") (pinfunction "I_11") (pintype "input"))
      (node (ref "E7") (pin "8") (pinfunction "~{Q}_8") (pintype "output"))
    )
    (net (code "64") (name "Net-(E8A-I0)") (class "Default")
      (node (ref "E8") (pin "1") (pinfunction "I0_1") (pintype "input"))
      (node (ref "E8") (pin "8") (pinfunction "O_8") (pintype "output"))
    )
    (net (code "65") (name "Net-(E10A-P$3)") (class "Default")
      (node (ref "E10") (pin "3") (pinfunction "P$3_3") (pintype "input"))
      (node (ref "E10") (pin "4") (pinfunction "P$4_4") (pintype "input"))
      (node (ref "E16") (pin "8") (pinfunction "~{Q}_8") (pintype "output"))
    )
    (net (code "66") (name "Net-(E10A-P$5)") (class "Default")
      (node (ref "C22") (pin "-") (pinfunction "-_-") (pintype "passive"))
      (node (ref "E10") (pin "11") (pinfunction "P$5_11") (pintype "bidirectional"))
    )
    (net (code "67") (name "Net-(E10A-P$6)") (class "Default")
      (node (ref "D1") (pin "C") (pinfunction "C_C") (pintype "passive"))
      (node (ref "E10") (pin "13") (pinfunction "P$6_13") (pintype "bidirectional"))
    )
    (net (code "68") (name "Net-(E10A-~{Q})") (class "Default")
      (node (ref "E10") (pin "6") (pinfunction "~{Q}_6") (pintype "output"))
      (node (ref "E12") (pin "2") (pinfunction "I0_2") (pintype "input"))
      (node (ref "E12") (pin "3") (pinfunction "I1_3") (pintype "input"))
      (node (ref "E12") (pin "5") (pinfunction "I0_5") (pintype "input"))
      (node (ref "E12") (pin "6") (pinfunction "I1_6") (pintype "input"))
      (node (ref "E16") (pin "10") (pinfunction "PRE_10") (pintype "input"))
      (node (ref "E9") (pin "3") (pinfunction "CLK_3") (pintype "input"))
    )
    (net (code "69") (name "Net-(E11A-O)") (class "Default")
      (node (ref "E11") (pin "8") (pinfunction "O_8") (pintype "output"))
      (node (ref "E14") (pin "12") (pinfunction "I0_12") (pintype "input"))
      (node (ref "E14") (pin "13") (pinfunction "I1_13") (pintype "input"))
    )
    (net (code "70") (name "Net-(E13A-I0)") (class "Default")
      (node (ref "E13") (pin "1") (pinfunction "I0_1") (pintype "input"))
      (node (ref "E16") (pin "9") (pinfunction "Q_9") (pintype "output"))
    )
    (net (code "71") (name "Net-(E13A-I1)") (class "Default")
      (node (ref "E13") (pin "2") (pinfunction "I1_2") (pintype "input"))
      (node (ref "E13") (pin "4") (pinfunction "I2_4") (pintype "input"))
      (node (ref "E13") (pin "5") (pinfunction "I3_5") (pintype "input"))
      (node (ref "E14") (pin "8") (pinfunction "O_8") (pintype "output"))
    )
    (net (code "72") (name "Net-(E14A-I1)") (class "Default")
      (node (ref "E14") (pin "2") (pinfunction "I1_2") (pintype "input"))
      (node (ref "E14") (pin "6") (pinfunction "O_6") (pintype "output"))
      (node (ref "E5") (pin "3") (pinfunction "P$3_3") (pintype "input"))
      (node (ref "E5") (pin "4") (pinfunction "P$4_4") (pintype "input"))
    )
    (net (code "73") (name "Net-(E14A-O)") (class "Default")
      (node (ref "E14") (pin "3") (pinfunction "O_3") (pintype "output"))
      (node (ref "E16") (pin "12") (pinfunction "D_12") (pintype "input"))
    )
    (net (code "74") (name "Net-(E14D-O)") (class "Default")
      (node (ref "E14") (pin "11") (pinfunction "O_11") (pintype "output"))
      (node (ref "E8") (pin "10") (pinfunction "I1_10") (pintype "input"))
      (node (ref "E8") (pin "13") (pinfunction "I1_13") (pintype "input"))
      (node (ref "E8") (pin "4") (pinfunction "I0_4") (pintype "input"))
    )
    (net (code "75") (name "Net-(E15A-P$5)") (class "Default")
      (node (ref "C23") (pin "-") (pinfunction "-_-") (pintype "passive"))
      (node (ref "E15") (pin "11") (pinfunction "P$5_11") (pintype "bidirectional"))
    )
    (net (code "76") (name "Net-(E15A-P$6)") (class "Default")
      (node (ref "D2") (pin "C") (pinfunction "C_C") (pintype "passive"))
      (node (ref "E15") (pin "13") (pinfunction "P$6_13") (pintype "bidirectional"))
    )
    (net (code "77") (name "Net-(E15A-~{Q})") (class "Default")
      (node (ref "E15") (pin "6") (pinfunction "~{Q}_6") (pintype "output"))
      (node (ref "E16") (pin "3") (pinfunction "CLK_3") (pintype "input"))
    )
    (net (code "78") (name "Net-(E16A-D)") (class "Default")
      (node (ref "E1") (pin "10") (pinfunction "PRE_10") (pintype "input"))
      (node (ref "E1") (pin "4") (pinfunction "PRE_4") (pintype "input"))
      (node (ref "E16") (pin "13") (pinfunction "CLR_13") (pintype "input"))
      (node (ref "E16") (pin "2") (pinfunction "D_2") (pintype "input"))
      (node (ref "E16") (pin "4") (pinfunction "PRE_4") (pintype "input"))
      (node (ref "E2") (pin "10") (pinfunction "PRE_10") (pintype "input"))
      (node (ref "E2") (pin "4") (pinfunction "PRE_4") (pintype "input"))
      (node (ref "E4") (pin "10") (pinfunction "PRE_10") (pintype "input"))
      (node (ref "E4") (pin "4") (pinfunction "PRE_4") (pintype "input"))
      (node (ref "E7") (pin "10") (pinfunction "PRE_10") (pintype "input"))
      (node (ref "E7") (pin "4") (pinfunction "PRE_4") (pintype "input"))
      (node (ref "E9") (pin "10") (pinfunction "PRE_10") (pintype "input"))
      (node (ref "E9") (pin "12") (pinfunction "D_12") (pintype "input"))
      (node (ref "R1") (pin "1") (pinfunction "1_1") (pintype "passive"))
    )
    (net (code "79") (name "Net-(Q1-B)") (class "Default")
      (node (ref "Q1") (pin "2") (pinfunction "B_2") (pintype "passive"))
      (node (ref "Q2") (pin "3") (pinfunction "C_3") (pintype "passive"))
      (node (ref "R10") (pin "2") (pinfunction "2_2") (pintype "passive"))
      (node (ref "R13") (pin "1") (pinfunction "1_1") (pintype "passive"))
    )
    (net (code "80") (name "Net-(Q1-E)") (class "Default")
      (node (ref "Q1") (pin "1") (pinfunction "E_1") (pintype "passive"))
      (node (ref "Q2") (pin "1") (pinfunction "E_1") (pintype "passive"))
      (node (ref "R12") (pin "1") (pinfunction "1_1") (pintype "passive"))
    )
    (net (code "81") (name "Net-(Q2-B)") (class "Default")
      (node (ref "C26") (pin "1") (pinfunction "1_1") (pintype "passive"))
      (node (ref "Q2") (pin "2") (pinfunction "B_2") (pintype "passive"))
      (node (ref "R11") (pin "2") (pinfunction "2_2") (pintype "passive"))
    )
    (net (code "82") (name "VCC") (class "Default")
      (node (ref "C1") (pin "1") (pinfunction "1_1") (pintype "passive"))
      (node (ref "C10") (pin "1") (pinfunction "1_1") (pintype "passive"))
      (node (ref "C11") (pin "1") (pinfunction "1_1") (pintype "passive"))
      (node (ref "C12") (pin "1") (pinfunction "1_1") (pintype "passive"))
      (node (ref "C13") (pin "1") (pinfunction "1_1") (pintype "passive"))
      (node (ref "C14") (pin "1") (pinfunction "1_1") (pintype "passive"))
      (node (ref "C15") (pin "1") (pinfunction "1_1") (pintype "passive"))
      (node (ref "C16") (pin "1") (pinfunction "1_1") (pintype "passive"))
      (node (ref "C17") (pin "1") (pinfunction "1_1") (pintype "passive"))
      (node (ref "C18") (pin "+") (pinfunction "+_+") (pintype "passive"))
      (node (ref "C19") (pin "+") (pinfunction "+_+") (pintype "passive"))
      (node (ref "C2") (pin "1") (pinfunction "1_1") (pintype "passive"))
      (node (ref "C20") (pin "+") (pinfunction "+_+") (pintype "passive"))
      (node (ref "C21") (pin "+") (pinfunction "+_+") (pintype "passive"))
      (node (ref "C3") (pin "1") (pinfunction "1_1") (pintype "passive"))
      (node (ref "C4") (pin "1") (pinfunction "1_1") (pintype "passive"))
      (node (ref "C5") (pin "1") (pinfunction "1_1") (pintype "passive"))
      (node (ref "C6") (pin "1") (pinfunction "1_1") (pintype "passive"))
      (node (ref "C7") (pin "1") (pinfunction "1_1") (pintype "passive"))
      (node (ref "C8") (pin "1") (pinfunction "1_1") (pintype "passive"))
      (node (ref "C9") (pin "1") (pinfunction "1_1") (pintype "passive"))
      (node (ref "R1") (pin "2") (pinfunction "2_2") (pintype "passive"))
      (node (ref "R12") (pin "2") (pinfunction "2_2") (pintype "passive"))
      (node (ref "R13") (pin "2") (pinfunction "2_2") (pintype "passive"))
      (node (ref "R14") (pin "2") (pinfunction "2_2") (pintype "passive"))
      (node (ref "R15") (pin "2") (pinfunction "2_2") (pintype "passive"))
      (node (ref "R2") (pin "2") (pinfunction "2_2") (pintype "passive"))
      (node (ref "R3") (pin "2") (pinfunction "2_2") (pintype "passive"))
      (node (ref "R5") (pin "2") (pinfunction "2_2") (pintype "passive"))
      (node (ref "R7") (pin "2") (pinfunction "2_2") (pintype "passive"))
      (node (ref "R8") (pin "2") (pinfunction "2_2") (pintype "passive"))
      (node (ref "U$2") (pin "AA2") (pinfunction "1_AA2") (pintype "bidirectional"))
      (node (ref "U$2") (pin "BA2") (pinfunction "1_BA2") (pintype "bidirectional"))
    )
    (net (code "83") (name "unconnected-(E1A-Q-Pad5)") (class "Default")
      (node (ref "E1") (pin "5") (pinfunction "Q_5") (pintype "output"))
    )
    (net (code "84") (name "unconnected-(E1B-Q-Pad9)") (class "Default")
      (node (ref "E1") (pin "9") (pinfunction "Q_9") (pintype "output"))
    )
    (net (code "85") (name "unconnected-(E2A-Q-Pad5)") (class "Default")
      (node (ref "E2") (pin "5") (pinfunction "Q_5") (pintype "output"))
    )
    (net (code "86") (name "unconnected-(E2B-Q-Pad9)") (class "Default")
      (node (ref "E2") (pin "9") (pinfunction "Q_9") (pintype "output"))
    )
    (net (code "87") (name "unconnected-(E4A-Q-Pad5)") (class "Default")
      (node (ref "E4") (pin "5") (pinfunction "Q_5") (pintype "output"))
    )
    (net (code "88") (name "unconnected-(E4B-Q-Pad9)") (class "Default")
      (node (ref "E4") (pin "9") (pinfunction "Q_9") (pintype "output"))
    )
    (net (code "89") (name "unconnected-(E5A-~{Q}-Pad6)") (class "Default")
      (node (ref "E5") (pin "6") (pinfunction "~{Q}_6") (pintype "output"))
    )
    (net (code "90") (name "unconnected-(E7A-Q-Pad5)") (class "Default")
      (node (ref "E7") (pin "5") (pinfunction "Q_5") (pintype "output"))
    )
    (net (code "91") (name "unconnected-(E7B-Q-Pad9)") (class "Default")
      (node (ref "E7") (pin "9") (pinfunction "Q_9") (pintype "output"))
    )
    (net (code "92") (name "unconnected-(E9A-Q-Pad5)") (class "Default")
      (node (ref "E9") (pin "5") (pinfunction "Q_5") (pintype "output"))
    )
    (net (code "93") (name "unconnected-(E9B-~{Q}-Pad8)") (class "Default")
      (node (ref "E9") (pin "8") (pinfunction "~{Q}_8") (pintype "output"))
    )
    (net (code "94") (name "unconnected-(E10A-Q-Pad8)") (class "Default")
      (node (ref "E10") (pin "8") (pinfunction "Q_8") (pintype "output"))
    )
    (net (code "95") (name "unconnected-(E15A-Q-Pad8)") (class "Default")
      (node (ref "E15") (pin "8") (pinfunction "Q_8") (pintype "output"))
    )
    (net (code "96") (name "unconnected-(E16A-~{Q}-Pad6)") (class "Default")
      (node (ref "E16") (pin "6") (pinfunction "~{Q}_6") (pintype "output"))
    )
  )
)
